# Driver.net
KiCad netlist of a schematic drawn in Altium Designer
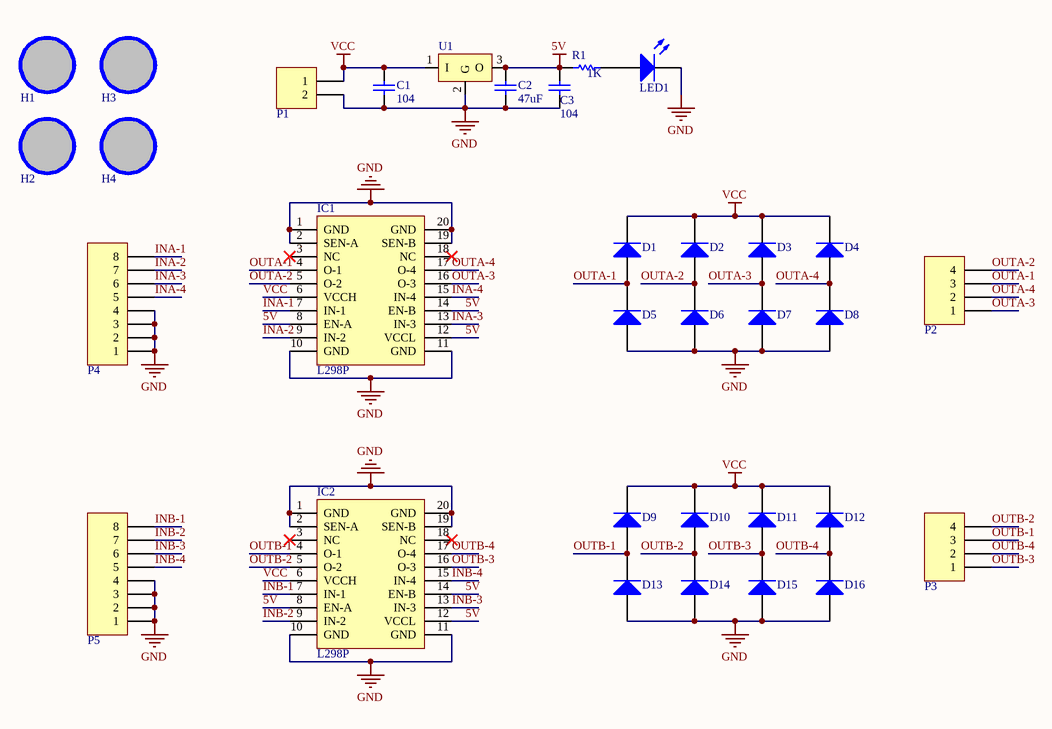
[diagram p0: Driver.SchDoc]

(export (version "E")
  (design (tool "Eeschema 10.0.6"))
  (components
    (comp (ref "C1")
      (value "104")
      (footprint "CAP-SM-0805")
      (description "Capacitor")
      (fields (field (name "Comment") "Cap Non-Pol SMD"))
      (libsource (lib "PIF_Library") (part "Cap Non-Pol SMD"))
    )
    (comp (ref "C2")
      (value "47uF")
      (footprint "CAP-2312")
      (description "Capacitor")
      (fields (field (name "Comment") "Cap Non-Pol SMD"))
      (libsource (lib "PIF_Library") (part "Cap Non-Pol SMD"))
    )
    (comp (ref "C3")
      (value "104")
      (footprint "CAP-SM-0805")
      (description "Capacitor")
      (fields (field (name "Comment") "Cap Non-Pol SMD"))
      (libsource (lib "PIF_Library") (part "Cap Non-Pol SMD"))
    )
    (comp (ref "D1") (value "Diode-S") (footprint "SS34") (libsource (lib "MYLIB") (part "Diode-S")))
    (comp (ref "D2") (value "Diode-S") (footprint "SS34") (libsource (lib "MYLIB") (part "Diode-S")))
    (comp (ref "D3") (value "Diode-S") (footprint "SS34") (libsource (lib "MYLIB") (part "Diode-S")))
    (comp (ref "D4") (value "Diode-S") (footprint "SS34") (libsource (lib "MYLIB") (part "Diode-S")))
    (comp (ref "D5") (value "Diode-S") (footprint "SS34") (libsource (lib "MYLIB") (part "Diode-S")))
    (comp (ref "D6") (value "Diode-S") (footprint "SS34") (libsource (lib "MYLIB") (part "Diode-S")))
    (comp (ref "D7") (value "Diode-S") (footprint "SS34") (libsource (lib "MYLIB") (part "Diode-S")))
    (comp (ref "D8") (value "Diode-S") (footprint "SS34") (libsource (lib "MYLIB") (part "Diode-S")))
    (comp (ref "D9") (value "Diode-S") (footprint "SS34") (libsource (lib "MYLIB") (part "Diode-S")))
    (comp (ref "D10") (value "Diode-S") (footprint "SS34") (libsource (lib "MYLIB") (part "Diode-S")))
    (comp (ref "D11") (value "Diode-S") (footprint "SS34") (libsource (lib "MYLIB") (part "Diode-S")))
    (comp (ref "D12") (value "Diode-S") (footprint "SS34") (libsource (lib "MYLIB") (part "Diode-S")))
    (comp (ref "D13") (value "Diode-S") (footprint "SS34") (libsource (lib "MYLIB") (part "Diode-S")))
    (comp (ref "D14") (value "Diode-S") (footprint "SS34") (libsource (lib "MYLIB") (part "Diode-S")))
    (comp (ref "D15") (value "Diode-S") (footprint "SS34") (libsource (lib "MYLIB") (part "Diode-S")))
    (comp (ref "D16") (value "Diode-S") (footprint "SS34") (libsource (lib "MYLIB") (part "Diode-S")))
    (comp (ref "H1")
      (value "Hole")
      (footprint "LO KHOAN 3MM")
      (description "Hole 3mm")
      (libsource (lib "PIF_Library") (part "Hole"))
    )
    (comp (ref "H2")
      (value "Hole")
      (footprint "LO KHOAN 3MM")
      (description "Hole 3mm")
      (libsource (lib "PIF_Library") (part "Hole"))
    )
    (comp (ref "H3")
      (value "Hole")
      (footprint "LO KHOAN 3MM")
      (description "Hole 3mm")
      (libsource (lib "PIF_Library") (part "Hole"))
    )
    (comp (ref "H4")
      (value "Hole")
      (footprint "LO KHOAN 3MM")
      (description "Hole 3mm")
      (libsource (lib "PIF_Library") (part "Hole"))
    )
    (comp (ref "IC1") (value "L298P") (footprint "L298P") (libsource (lib "MYLIB") (part "L298P")))
    (comp (ref "IC2") (value "L298P") (footprint "L298P") (libsource (lib "MYLIB") (part "L298P")))
    (comp (ref "LED1")
      (value "LED SMD")
      (footprint "LED_0805_Blue")
      (description "LED")
      (libsource (lib "PIF_Library") (part "LED SMD"))
    )
    (comp (ref "P1")
      (value "Domino 2")
      (footprint "DOMINO 2- 5mm")
      (description "Domino, 2-Pin")
      (fields (field (name "PUBLISHER") "Altium Limited"))
      (libsource (lib "PIF_Library") (part "Domino 2"))
    )
    (comp (ref "P2")
      (value "Domino 4")
      (footprint "DOMINO 4 -5mm")
      (description "Domino 4-Pin")
      (fields (field (name "PUBLISHER") "Altium Limited"))
      (libsource (lib "PIF_Library") (part "Domino 4"))
    )
    (comp (ref "P3")
      (value "Domino 4")
      (footprint "DOMINO 4 -5mm")
      (description "Domino 4-Pin")
      (fields (field (name "PUBLISHER") "Altium Limited"))
      (libsource (lib "PIF_Library") (part "Domino 4"))
    )
    (comp (ref "P4")
      (value "Header 8")
      (footprint "JP8")
      (description "Header, 8-Pin")
      (fields (field (name "PUBLISHER") "Altium Limited"))
      (libsource (lib "PIF_Library") (part "Header 8"))
    )
    (comp (ref "P5")
      (value "Header 8")
      (footprint "JP8")
      (description "Header, 8-Pin")
      (fields (field (name "PUBLISHER") "Altium Limited"))
      (libsource (lib "PIF_Library") (part "Header 8"))
    )
    (comp (ref "R1")
      (value "1K")
      (footprint "RES-SM-0805")
      (description "Resistor")
      (fields (field (name "Comment") "RESISTOR SMD"))
      (libsource (lib "PIF_Library") (part "RESISTOR SMD"))
    )
    (comp (ref "U1")
      (value "LM78xx")
      (footprint "TO252-123")
      (description "Positive Voltage Regulator")
      (fields (field (name "PUBLISHER") "Altium Limited"))
      (libsource (lib "LIBRARY") (part "LM78xx"))
    )
  )
  (nets
    (net (code "1") (name "/INA-1") (class "Default")
      (node (ref "IC1") (pin "7") (pinfunction "IN-1_7") (pintype "passive"))
      (node (ref "P4") (pin "8") (pinfunction "8_8") (pintype "passive"))
    )
    (net (code "2") (name "/INA-2") (class "Default")
      (node (ref "IC1") (pin "9") (pinfunction "IN-2_9") (pintype "passive"))
      (node (ref "P4") (pin "7") (pinfunction "7_7") (pintype "passive"))
    )
    (net (code "3") (name "/INA-3") (class "Default")
      (node (ref "IC1") (pin "13") (pinfunction "IN-3_13") (pintype "passive"))
      (node (ref "P4") (pin "6") (pinfunction "6_6") (pintype "passive"))
    )
    (net (code "4") (name "/INA-4") (class "Default")
      (node (ref "IC1") (pin "15") (pinfunction "IN-4_15") (pintype "passive"))
      (node (ref "P4") (pin "5") (pinfunction "5_5") (pintype "passive"))
    )
    (net (code "5") (name "/INB-1") (class "Default")
      (node (ref "IC2") (pin "7") (pinfunction "IN-1_7") (pintype "passive"))
      (node (ref "P5") (pin "8") (pinfunction "8_8") (pintype "passive"))
    )
    (net (code "6") (name "/INB-2") (class "Default")
      (node (ref "IC2") (pin "9") (pinfunction "IN-2_9") (pintype "passive"))
      (node (ref "P5") (pin "7") (pinfunction "7_7") (pintype "passive"))
    )
    (net (code "7") (name "/INB-3") (class "Default")
      (node (ref "IC2") (pin "13") (pinfunction "IN-3_13") (pintype "passive"))
      (node (ref "P5") (pin "6") (pinfunction "6_6") (pintype "passive"))
    )
    (net (code "8") (name "/INB-4") (class "Default")
      (node (ref "IC2") (pin "15") (pinfunction "IN-4_15") (pintype "passive"))
      (node (ref "P5") (pin "5") (pinfunction "5_5") (pintype "passive"))
    )
    (net (code "9") (name "/OUTA-1") (class "Default")
      (node (ref "D1") (pin "2") (pinfunction "K_2") (pintype "passive"))
      (node (ref "D5") (pin "1") (pinfunction "A_1") (pintype "passive"))
      (node (ref "IC1") (pin "4") (pinfunction "O-1_4") (pintype "passive"))
      (node (ref "P2") (pin "3") (pinfunction "3_3") (pintype "passive"))
    )
    (net (code "10") (name "/OUTA-2") (class "Default")
      (node (ref "D2") (pin "2") (pinfunction "K_2") (pintype "passive"))
      (node (ref "D6") (pin "1") (pinfunction "A_1") (pintype "passive"))
      (node (ref "IC1") (pin "5") (pinfunction "O-2_5") (pintype "passive"))
      (node (ref "P2") (pin "4") (pinfunction "4_4") (pintype "passive"))
    )
    (net (code "11") (name "/OUTA-3") (class "Default")
      (node (ref "D3") (pin "2") (pinfunction "K_2") (pintype "passive"))
      (node (ref "D7") (pin "1") (pinfunction "A_1") (pintype "passive"))
      (node (ref "IC1") (pin "16") (pinfunction "O-3_16") (pintype "passive"))
      (node (ref "P2") (pin "1") (pinfunction "1_1") (pintype "passive"))
    )
    (net (code "12") (name "/OUTA-4") (class "Default")
      (node (ref "D4") (pin "2") (pinfunction "K_2") (pintype "passive"))
      (node (ref "D8") (pin "1") (pinfunction "A_1") (pintype "passive"))
      (node (ref "IC1") (pin "17") (pinfunction "O-4_17") (pintype "passive"))
      (node (ref "P2") (pin "2") (pinfunction "2_2") (pintype "passive"))
    )
    (net (code "13") (name "/OUTB-1") (class "Default")
      (node (ref "D13") (pin "1") (pinfunction "A_1") (pintype "passive"))
      (node (ref "D9") (pin "2") (pinfunction "K_2") (pintype "passive"))
      (node (ref "IC2") (pin "4") (pinfunction "O-1_4") (pintype "passive"))
      (node (ref "P3") (pin "3") (pinfunction "3_3") (pintype "passive"))
    )
    (net (code "14") (name "/OUTB-2") (class "Default")
      (node (ref "D10") (pin "2") (pinfunction "K_2") (pintype "passive"))
      (node (ref "D14") (pin "1") (pinfunction "A_1") (pintype "passive"))
      (node (ref "IC2") (pin "5") (pinfunction "O-2_5") (pintype "passive"))
      (node (ref "P3") (pin "4") (pinfunction "4_4") (pintype "passive"))
    )
    (net (code "15") (name "/OUTB-3") (class "Default")
      (node (ref "D11") (pin "2") (pinfunction "K_2") (pintype "passive"))
      (node (ref "D15") (pin "1") (pinfunction "A_1") (pintype "passive"))
      (node (ref "IC2") (pin "16") (pinfunction "O-3_16") (pintype "passive"))
      (node (ref "P3") (pin "1") (pinfunction "1_1") (pintype "passive"))
    )
    (net (code "16") (name "/OUTB-4") (class "Default")
      (node (ref "D12") (pin "2") (pinfunction "K_2") (pintype "passive"))
      (node (ref "D16") (pin "1") (pinfunction "A_1") (pintype "passive"))
      (node (ref "IC2") (pin "17") (pinfunction "O-4_17") (pintype "passive"))
      (node (ref "P3") (pin "2") (pinfunction "2_2") (pintype "passive"))
    )
    (net (code "17") (name "5V") (class "Default")
      (node (ref "C2") (pin "2") (pinfunction "2_2") (pintype "passive"))
      (node (ref "C3") (pin "2") (pinfunction "2_2") (pintype "passive"))
      (node (ref "IC1") (pin "12") (pinfunction "VCCL_12") (pintype "passive"))
      (node (ref "IC1") (pin "14") (pinfunction "EN-B_14") (pintype "passive"))
      (node (ref "IC1") (pin "8") (pinfunction "EN-A_8") (pintype "passive"))
      (node (ref "IC2") (pin "12") (pinfunction "VCCL_12") (pintype "passive"))
      (node (ref "IC2") (pin "14") (pinfunction "EN-B_14") (pintype "passive"))
      (node (ref "IC2") (pin "8") (pinfunction "EN-A_8") (pintype "passive"))
      (node (ref "R1") (pin "1") (pinfunction "1_1") (pintype "passive"))
      (node (ref "U1") (pin "3") (pinfunction "O_3") (pintype "power_in"))
    )
    (net (code "18") (name "GND") (class "Default")
      (node (ref "C1") (pin "1") (pinfunction "1_1") (pintype "passive"))
      (node (ref "C2") (pin "1") (pinfunction "1_1") (pintype "passive"))
      (node (ref "C3") (pin "1") (pinfunction "1_1") (pintype "passive"))
      (node (ref "D13") (pin "2") (pinfunction "K_2") (pintype "passive"))
      (node (ref "D14") (pin "2") (pinfunction "K_2") (pintype "passive"))
      (node (ref "D15") (pin "2") (pinfunction "K_2") (pintype "passive"))
      (node (ref "D16") (pin "2") (pinfunction "K_2") (pintype "passive"))
      (node (ref "D5") (pin "2") (pinfunction "K_2") (pintype "passive"))
      (node (ref "D6") (pin "2") (pinfunction "K_2") (pintype "passive"))
      (node (ref "D7") (pin "2") (pinfunction "K_2") (pintype "passive"))
      (node (ref "D8") (pin "2") (pinfunction "K_2") (pintype "passive"))
      (node (ref "IC1") (pin "1") (pinfunction "GND_1") (pintype "passive"))
      (node (ref "IC1") (pin "10") (pinfunction "GND_10") (pintype "passive"))
      (node (ref "IC1") (pin "11") (pinfunction "GND_11") (pintype "passive"))
      (node (ref "IC1") (pin "19") (pinfunction "SEN-B_19") (pintype "passive"))
      (node (ref "IC1") (pin "2") (pinfunction "SEN-A_2") (pintype "passive"))
      (node (ref "IC1") (pin "20") (pinfunction "GND_20") (pintype "passive"))
      (node (ref "IC2") (pin "1") (pinfunction "GND_1") (pintype "passive"))
      (node (ref "IC2") (pin "10") (pinfunction "GND_10") (pintype "passive"))
      (node (ref "IC2") (pin "11") (pinfunction "GND_11") (pintype "passive"))
      (node (ref "IC2") (pin "19") (pinfunction "SEN-B_19") (pintype "passive"))
      (node (ref "IC2") (pin "2") (pinfunction "SEN-A_2") (pintype "passive"))
      (node (ref "IC2") (pin "20") (pinfunction "GND_20") (pintype "passive"))
      (node (ref "LED1") (pin "2") (pinfunction "K_2") (pintype "passive"))
      (node (ref "P1") (pin "2") (pinfunction "2_2") (pintype "passive"))
      (node (ref "P4") (pin "1") (pinfunction "1_1") (pintype "passive"))
      (node (ref "P4") (pin "2") (pinfunction "2_2") (pintype "passive"))
      (node (ref "P4") (pin "3") (pinfunction "3_3") (pintype "passive"))
      (node (ref "P4") (pin "4") (pinfunction "4_4") (pintype "passive"))
      (node (ref "P5") (pin "1") (pinfunction "1_1") (pintype "passive"))
      (node (ref "P5") (pin "2") (pinfunction "2_2") (pintype "passive"))
      (node (ref "P5") (pin "3") (pinfunction "3_3") (pintype "passive"))
      (node (ref "P5") (pin "4") (pinfunction "4_4") (pintype "passive"))
      (node (ref "U1") (pin "2") (pinfunction "G_2") (pintype "power_in"))
    )
    (net (code "19") (name "Net-(LED1-A)") (class "Default")
      (node (ref "LED1") (pin "1") (pinfunction "A_1") (pintype "passive"))
      (node (ref "R1") (pin "2") (pinfunction "2_2") (pintype "passive"))
    )
    (net (code "20") (name "VCC") (class "Default")
      (node (ref "C1") (pin "2") (pinfunction "2_2") (pintype "passive"))
      (node (ref "D1") (pin "1") (pinfunction "A_1") (pintype "passive"))
      (node (ref "D10") (pin "1") (pinfunction "A_1") (pintype "passive"))
      (node (ref "D11") (pin "1") (pinfunction "A_1") (pintype "passive"))
      (node (ref "D12") (pin "1") (pinfunction "A_1") (pintype "passive"))
      (node (ref "D2") (pin "1") (pinfunction "A_1") (pintype "passive"))
      (node (ref "D3") (pin "1") (pinfunction "A_1") (pintype "passive"))
      (node (ref "D4") (pin "1") (pinfunction "A_1") (pintype "passive"))
      (node (ref "D9") (pin "1") (pinfunction "A_1") (pintype "passive"))
      (node (ref "IC1") (pin "6") (pinfunction "VCCH_6") (pintype "passive"))
      (node (ref "IC2") (pin "6") (pinfunction "VCCH_6") (pintype "passive"))
      (node (ref "P1") (pin "1") (pinfunction "1_1") (pintype "passive"))
      (node (ref "U1") (pin "1") (pinfunction "I_1") (pintype "power_in"))
    )
    (net (code "21") (name "unconnected-(H1-Pad1)") (class "Default")
      (node (ref "H1") (pin "1") (pinfunction "1_1") (pintype "passive"))
    )
    (net (code "22") (name "unconnected-(H2-Pad1)") (class "Default")
      (node (ref "H2") (pin "1") (pinfunction "1_1") (pintype "passive"))
    )
    (net (code "23") (name "unconnected-(H3-Pad1)") (class "Default")
      (node (ref "H3") (pin "1") (pinfunction "1_1") (pintype "passive"))
    )
    (net (code "24") (name "unconnected-(H4-Pad1)") (class "Default")
      (node (ref "H4") (pin "1") (pinfunction "1_1") (pintype "passive"))
    )
    (net (code "25") (name "unconnected-(IC1-NC-Pad3)") (class "Default")
      (node (ref "IC1") (pin "3") (pinfunction "NC_3") (pintype "passive+no_connect"))
    )
    (net (code "26") (name "unconnected-(IC1-NC-Pad18)") (class "Default")
      (node (ref "IC1") (pin "18") (pinfunction "NC_18") (pintype "passive+no_connect"))
    )
    (net (code "27") (name "unconnected-(IC2-NC-Pad3)") (class "Default")
      (node (ref "IC2") (pin "3") (pinfunction "NC_3") (pintype "passive+no_connect"))
    )
    (net (code "28") (name "unconnected-(IC2-NC-Pad18)") (class "Default")
      (node (ref "IC2") (pin "18") (pinfunction "NC_18") (pintype "passive+no_connect"))
    )
  )
)
